# CC2538_Power_Circuit.net
KiCad netlist of a schematic drawn in Altium Designer
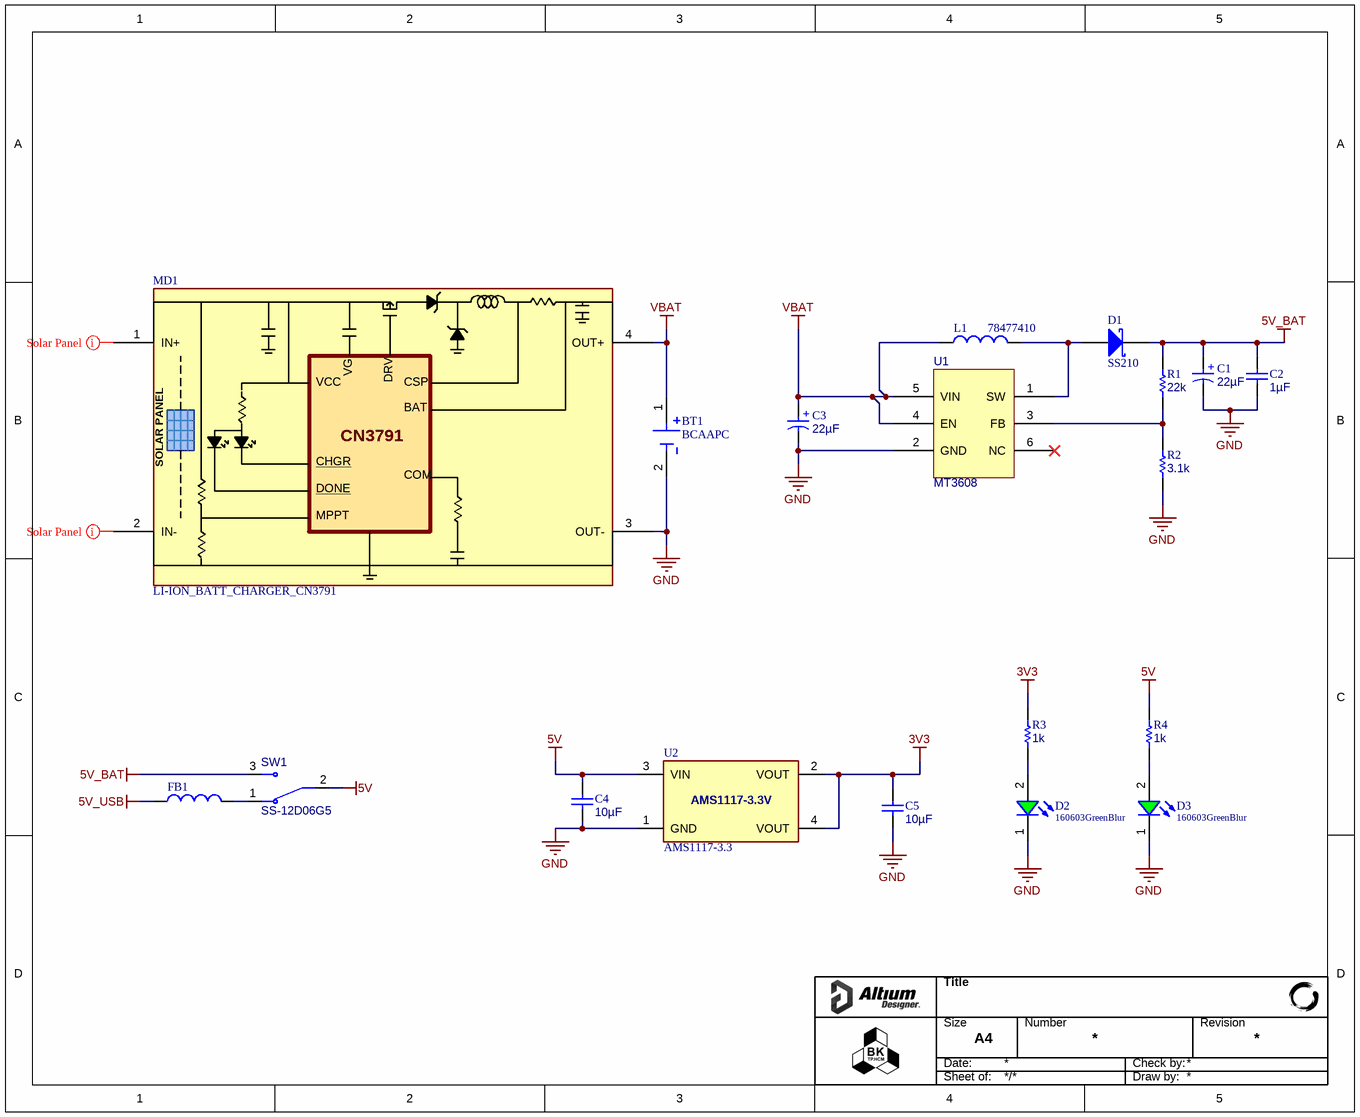
[diagram p0: [CC2538] Power Circuit.SchDoc]

(export (version "E")
  (design (tool "Eeschema 10.0.6"))
  (components
    (comp (ref "BT1")
      (value "BCAAPC")
      (footprint "BCAAC")
      (description "Battery Holder (Open) AA 1 Cell PC Pin")
      (libsource (lib "University of Technology") (part "BCAAPC"))
    )
    (comp (ref "C1")
      (value "22µF")
      (footprint "WCAP-ASLI_D4H5.5")
      (description "V-Chip, D4 x H5.5mm, 22uF, 16V")
      (fields (field (name "MANUFACTURER") "Wurth Elektronik") (field (name "Comment") "865080340003"))
      (libsource (lib "University of Technology") (part "0710101508650801570160U20"))
    )
    (comp (ref "C2")
      (value "1µF")
      (footprint "CAP_0603")
      (description "CAP, size 0603, 1 uF, 16 VDC, 10%")
      (fields
        (field (name "MANUFACTURER PART NUMBER") "CL10B105KO8NNWC")
        (field (name "TOLERANCE") "10%")
        (field (name "SOURCE") "Capacitor_0603_10_percent.SchLib")
      )
      (libsource (lib "University of Technology") (part "010603475106.3"))
    )
    (comp (ref "C3")
      (value "22µF")
      (footprint "WCAP-ASLI_D4H5.5")
      (description "V-Chip, D4 x H5.5mm, 22uF, 16V")
      (fields (field (name "MANUFACTURER") "Wurth Elektronik") (field (name "Comment") "865080340003"))
      (libsource (lib "University of Technology") (part "0710101508650801570160U20"))
    )
    (comp (ref "C4")
      (value "10µF")
      (footprint "CAP_0603")
      (description "CAP, size 0603, 10 uF, 10 VDC, 10%")
      (fields
        (field (name "MANUFACTURER") "Samsung Electro-Mechanics")
        (field (name "LCSC PART #") "C19702")
        (field (name "SOURCE") "Capacitor_0603_10_percent.SchLib")
      )
      (libsource (lib "University of Technology") (part "010603475106.3"))
    )
    (comp (ref "C5")
      (value "10µF")
      (footprint "CAP_0603")
      (description "CAP, size 0603, 10 uF, 10 VDC, 10%")
      (fields
        (field (name "MANUFACTURER") "Samsung Electro-Mechanics")
        (field (name "LCSC PART #") "C19702")
        (field (name "SOURCE") "Capacitor_0603_10_percent.SchLib")
      )
      (libsource (lib "University of Technology") (part "010603475106.3"))
    )
    (comp (ref "D1")
      (value "SS210")
      (footprint "SS210-Footprint-SMA")
      (description "Rectifier Diode, Schottky, 1 Phase, 1 Element, 1.5A, 100V V(RRM), Silicon, DO-214AA")
      (libsource (lib "University of Technology") (part "SS210"))
    )
    (comp (ref "D2")
      (value "160603GreenBlur")
      (footprint "WL-SMCW_0603_H=0.7mm")
      (description "WL-SMCW SMT Mono-color Chip LED Blur, size 0603, Green, 3.2V, 140deg")
      (libsource (lib "University of Technology") (part "160603GreenClear"))
    )
    (comp (ref "D3")
      (value "160603GreenBlur")
      (footprint "WL-SMCW_0603_H=0.7mm")
      (description "WL-SMCW SMT Mono-color Chip LED Blur, size 0603, Green, 3.2V, 140deg")
      (libsource (lib "University of Technology") (part "160603GreenClear"))
    )
    (comp (ref "FB1")
      (value "CBG160808U601T")
      (footprint "CBG160808U601T-Footprint")
      (description "0603 600Ω ±25% DCR=0.5Ω 0.2A")
      (libsource (lib "University of Technology") (part "IND-2_1"))
    )
    (comp (ref "L1")
      (value "78477410")
      (footprint "WE-PD2A_4D28 (4730)")
      (description "General Purpose Inductor")
      (libsource (lib "University of Technology") (part "IND-2_1"))
    )
    (comp (ref "MD1")
      (value "LI-ION_BATT_CHARGER_CN3791")
      (footprint "LI-ION_BATT_CHARGER_CN3791-Footprint-1")
      (libsource (lib "University of Technology") (part "LI-ION_BATT_CHARGER_CN3791"))
    )
    (comp (ref "R1")
      (value "22k")
      (footprint "RES_0603")
      (description "RES, size 0603, 22 KOhm, 1/10 W, 1%")
      (fields (field (name "MANUFACTURER") "OEM") (field (name "TOLERANCE") "1%"))
      (libsource (lib "University of Technology") (part "00060371541"))
    )
    (comp (ref "R2")
      (value "3.1k")
      (footprint "RES_0603")
      (description "RES, size 0603, 3.1  KOhm, 1/10 W, 1%")
      (fields (field (name "MANUFACTURER PART NUMBER") "OEM") (field (name "TOLERANCE") "1%"))
      (libsource (lib "University of Technology") (part "00060371541"))
    )
    (comp (ref "R3")
      (value "1k")
      (footprint "RES_0603")
      (description "RES, size 0603, 1 KOhm, 1/10 W, 1%")
      (fields (field (name "TOLERANCE") "1%") (field (name "MANUFACTURER PART NUMBER") "RC0603FR-071KL"))
      (libsource (lib "University of Technology") (part "00060371541"))
    )
    (comp (ref "R4")
      (value "1k")
      (footprint "RES_0603")
      (description "RES, size 0603, 1 KOhm, 1/10 W, 1%")
      (fields (field (name "TOLERANCE") "1%") (field (name "MANUFACTURER PART NUMBER") "RC0603FR-071KL"))
      (libsource (lib "University of Technology") (part "00060371541"))
    )
    (comp (ref "SW1")
      (value "SS-12D06G5")
      (footprint "SS-12D06G5-Footprint")
      (libsource (lib "University of Technology") (part "SS-12D06G5-Symbol"))
    )
    (comp (ref "U1")
      (value "MT3608")
      (footprint "SOT95P280X145-6N")
      (description "1.2MHz 2A Vi=2V~24V Vo=28V(Max)")
      (libsource (lib "University of Technology") (part "MT3608"))
    )
    (comp (ref "U2")
      (value "AMS1117-3.3")
      (footprint "FP-AMS1117-IPC_B")
      (description "Fixed Positive LDO Regulator, 3.3V, 1.3V Dropout, PDSO3")
      (libsource (lib "University of Technology") (part "8bdbb5f8e77002000e30dd2845d0354_1"))
    )
  )
  (nets
    (net (code "1") (name "3V3") (class "Default")
      (node (ref "C5") (pin "2") (pinfunction "2_2") (pintype "passive"))
      (node (ref "R3") (pin "2") (pinfunction "2_2") (pintype "passive"))
      (node (ref "U2") (pin "2") (pinfunction "VOUT_2") (pintype "passive"))
      (node (ref "U2") (pin "4") (pinfunction "VOUT_4") (pintype "passive"))
    )
    (net (code "2") (name "5V") (class "Default")
      (node (ref "C4") (pin "2") (pinfunction "2_2") (pintype "passive"))
      (node (ref "R4") (pin "2") (pinfunction "2_2") (pintype "passive"))
      (node (ref "SW1") (pin "2") (pinfunction "2_2") (pintype "passive"))
      (node (ref "U2") (pin "3") (pinfunction "VIN_3") (pintype "power_in"))
    )
    (net (code "3") (name "5V_BAT") (class "Default")
      (node (ref "C1") (pin "1") (pinfunction "P_1") (pintype "passive"))
      (node (ref "C2") (pin "2") (pinfunction "2_2") (pintype "passive"))
      (node (ref "D1") (pin "2") (pinfunction "K_2") (pintype "passive"))
      (node (ref "R1") (pin "2") (pinfunction "2_2") (pintype "passive"))
      (node (ref "SW1") (pin "3") (pinfunction "3_3") (pintype "passive"))
    )
    (net (code "4") (name "5V_USB") (class "Default")
      (node (ref "FB1") (pin "1") (pinfunction "1_1") (pintype "passive"))
    )
    (net (code "5") (name "GND") (class "Default")
      (node (ref "BT1") (pin "2") (pinfunction "NEG_2") (pintype "passive"))
      (node (ref "C1") (pin "2") (pinfunction "N_2") (pintype "passive"))
      (node (ref "C2") (pin "1") (pinfunction "1_1") (pintype "passive"))
      (node (ref "C3") (pin "2") (pinfunction "N_2") (pintype "passive"))
      (node (ref "C4") (pin "1") (pinfunction "1_1") (pintype "passive"))
      (node (ref "C5") (pin "1") (pinfunction "1_1") (pintype "passive"))
      (node (ref "D2") (pin "1") (pinfunction "K_1") (pintype "passive"))
      (node (ref "D3") (pin "1") (pinfunction "K_1") (pintype "passive"))
      (node (ref "MD1") (pin "3") (pinfunction "OUT-_3") (pintype "passive"))
      (node (ref "R2") (pin "1") (pinfunction "1_1") (pintype "passive"))
      (node (ref "U1") (pin "2") (pinfunction "GND_2") (pintype "passive"))
      (node (ref "U2") (pin "1") (pinfunction "GND_1") (pintype "power_in"))
    )
    (net (code "6") (name "Net-(D1-A)") (class "Default")
      (node (ref "D1") (pin "1") (pinfunction "A_1") (pintype "passive"))
      (node (ref "L1") (pin "2") (pinfunction "2_2") (pintype "passive"))
      (node (ref "U1") (pin "1") (pinfunction "SW_1") (pintype "passive"))
    )
    (net (code "7") (name "Net-(D2-A)") (class "Default")
      (node (ref "D2") (pin "2") (pinfunction "A_2") (pintype "passive"))
      (node (ref "R3") (pin "1") (pinfunction "1_1") (pintype "passive"))
    )
    (net (code "8") (name "Net-(D3-A)") (class "Default")
      (node (ref "D3") (pin "2") (pinfunction "A_2") (pintype "passive"))
      (node (ref "R4") (pin "1") (pinfunction "1_1") (pintype "passive"))
    )
    (net (code "9") (name "Net-(FB1-Pad2)") (class "Default")
      (node (ref "FB1") (pin "2") (pinfunction "2_2") (pintype "passive"))
      (node (ref "SW1") (pin "1") (pinfunction "1_1") (pintype "passive"))
    )
    (net (code "10") (name "Net-(U1-FB)") (class "Default")
      (node (ref "R1") (pin "1") (pinfunction "1_1") (pintype "passive"))
      (node (ref "R2") (pin "2") (pinfunction "2_2") (pintype "passive"))
      (node (ref "U1") (pin "3") (pinfunction "FB_3") (pintype "passive"))
    )
    (net (code "11") (name "VBAT") (class "Default")
      (node (ref "BT1") (pin "1") (pinfunction "POS_1") (pintype "passive"))
      (node (ref "C3") (pin "1") (pinfunction "P_1") (pintype "passive"))
      (node (ref "L1") (pin "1") (pinfunction "1_1") (pintype "passive"))
      (node (ref "MD1") (pin "4") (pinfunction "OUT+_4") (pintype "passive"))
      (node (ref "U1") (pin "4") (pinfunction "EN_4") (pintype "passive"))
      (node (ref "U1") (pin "5") (pinfunction "VIN_5") (pintype "passive"))
    )
    (net (code "12") (name "unconnected-(MD1-IN+-Pad1)") (class "Default")
      (node (ref "MD1") (pin "1") (pinfunction "IN+_1") (pintype "passive"))
    )
    (net (code "13") (name "unconnected-(MD1-IN--Pad2)") (class "Default")
      (node (ref "MD1") (pin "2") (pinfunction "IN-_2") (pintype "passive"))
    )
    (net (code "14") (name "unconnected-(U1-NC-Pad6)") (class "Default")
      (node (ref "U1") (pin "6") (pinfunction "NC_6") (pintype "passive+no_connect"))
    )
  )
)
